# lightdimmer_rc.net
KiCad netlist of a schematic drawn in EAGLE
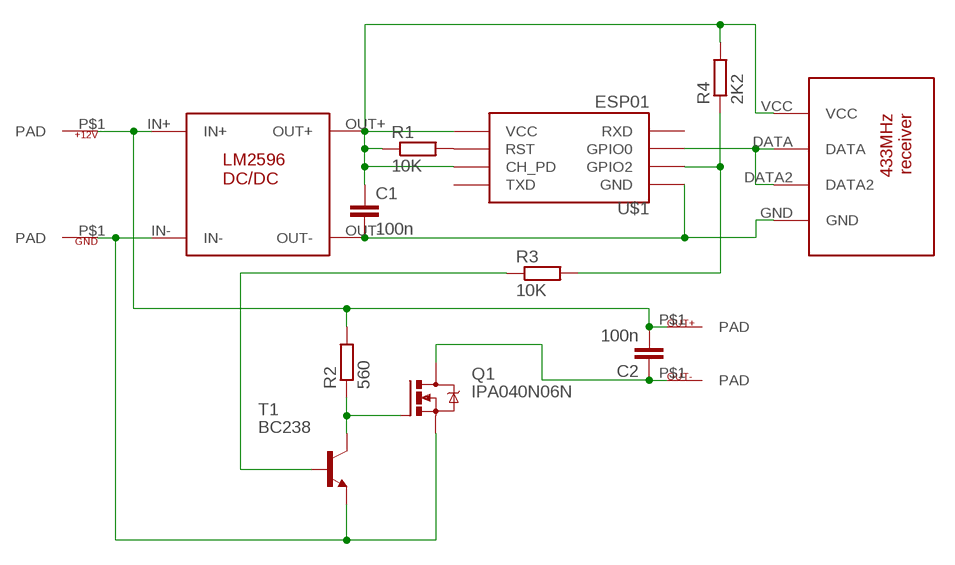
[diagram p0: schematic, sheet 1]

(export (version "E")
  (design (tool "Eeschema 10.0.6"))
  (components
    (comp (ref "+12V")
      (value "PAD")
      (footprint "eagle-import:PAD")
      (libsource (lib "eagle-import") (part "PAD"))
    )
    (comp (ref "C1")
      (value "100n")
      (footprint "eagle-import:C050-025X075")
      (libsource (lib "eagle-import") (part "C-EU050-025X075"))
    )
    (comp (ref "C2")
      (value "100n")
      (footprint "eagle-import:C050-025X075")
      (libsource (lib "eagle-import") (part "C-EU050-025X075"))
    )
    (comp (ref "GND")
      (value "PAD")
      (footprint "eagle-import:PAD")
      (libsource (lib "eagle-import") (part "PAD"))
    )
    (comp (ref "OUT+")
      (value "PAD")
      (footprint "eagle-import:PAD")
      (libsource (lib "eagle-import") (part "PAD"))
    )
    (comp (ref "OUT-")
      (value "PAD")
      (footprint "eagle-import:PAD")
      (libsource (lib "eagle-import") (part "PAD"))
    )
    (comp (ref "Q1")
      (value "IPA040N06N")
      (footprint "eagle-import:TO220BV")
      (libsource (lib "eagle-import") (part "IRF520"))
    )
    (comp (ref "R1")
      (value "10K")
      (footprint "eagle-import:0204_7")
      (libsource (lib "eagle-import") (part "R-EU_0204/7"))
    )
    (comp (ref "R2")
      (value "560")
      (footprint "eagle-import:0204_7")
      (libsource (lib "eagle-import") (part "R-EU_0204/7"))
    )
    (comp (ref "R3")
      (value "10K")
      (footprint "eagle-import:0204_7")
      (libsource (lib "eagle-import") (part "R-EU_0204/7"))
    )
    (comp (ref "R4")
      (value "2K2")
      (footprint "eagle-import:0204_7")
      (libsource (lib "eagle-import") (part "R-EU_0204/7"))
    )
    (comp (ref "T1")
      (value "BC238")
      (footprint "eagle-import:TO92-CBE")
      (libsource (lib "eagle-import") (part "-NPN-TO92-CBEBC238"))
    )
    (comp (ref "U$1")
      (value "ESP01")
      (footprint "eagle-import:ESP01")
      (libsource (lib "eagle-import") (part "ESP01"))
    )
    (comp (ref "U$2")
      (value "RECV433MHZ")
      (footprint "eagle-import:RECV433MHZ")
      (libsource (lib "eagle-import") (part "RECV433MHZ"))
    )
    (comp (ref "U$3")
      (value "LM2596DCDC")
      (footprint "eagle-import:LM2596DCDC")
      (libsource (lib "eagle-import") (part "LM2596DCDC"))
    )
  )
  (nets
    (net (code "1") (name "Net-(+12V-PAD)") (class "Default")
      (node (ref "+12V") (pin "P$1") (pinfunction "PAD_P$1") (pintype "bidirectional"))
      (node (ref "C2") (pin "2") (pinfunction "2_2") (pintype "passive"))
      (node (ref "OUT+") (pin "P$1") (pinfunction "PAD_P$1") (pintype "bidirectional"))
      (node (ref "R2") (pin "2") (pinfunction "2_2") (pintype "passive"))
      (node (ref "U$3") (pin "IN+") (pinfunction "IN+_IN+") (pintype "bidirectional"))
    )
    (net (code "2") (name "Net-(C1-Pad1)") (class "Default")
      (node (ref "C1") (pin "1") (pinfunction "1_1") (pintype "passive"))
      (node (ref "R1") (pin "1") (pinfunction "1_1") (pintype "passive"))
      (node (ref "R4") (pin "2") (pinfunction "2_2") (pintype "passive"))
      (node (ref "U$1") (pin "CH_PD") (pinfunction "CH_PD_CH_PD") (pintype "bidirectional"))
      (node (ref "U$1") (pin "VCC") (pinfunction "VCC_VCC") (pintype "bidirectional"))
      (node (ref "U$2") (pin "VCC") (pinfunction "VCC_VCC") (pintype "bidirectional"))
      (node (ref "U$3") (pin "OUT+") (pinfunction "OUT+_OUT+") (pintype "bidirectional"))
    )
    (net (code "3") (name "Net-(C1-Pad2)") (class "Default")
      (node (ref "C1") (pin "2") (pinfunction "2_2") (pintype "passive"))
      (node (ref "U$1") (pin "GND") (pinfunction "GND_GND") (pintype "bidirectional"))
      (node (ref "U$2") (pin "GND") (pinfunction "GND_GND") (pintype "bidirectional"))
      (node (ref "U$3") (pin "OUT-") (pinfunction "OUT-_OUT-") (pintype "bidirectional"))
    )
    (net (code "4") (name "Net-(GND-PAD)") (class "Default")
      (node (ref "GND") (pin "P$1") (pinfunction "PAD_P$1") (pintype "bidirectional"))
      (node (ref "Q1") (pin "S") (pinfunction "S_S") (pintype "passive"))
      (node (ref "T1") (pin "E") (pinfunction "E_E") (pintype "passive"))
      (node (ref "U$3") (pin "IN-") (pinfunction "IN-_IN-") (pintype "bidirectional"))
    )
    (net (code "5") (name "Net-(OUT--PAD)") (class "Default")
      (node (ref "C2") (pin "1") (pinfunction "1_1") (pintype "passive"))
      (node (ref "OUT-") (pin "P$1") (pinfunction "PAD_P$1") (pintype "bidirectional"))
      (node (ref "Q1") (pin "D") (pinfunction "D_D") (pintype "passive"))
    )
    (net (code "6") (name "Net-(Q1-PadG)") (class "Default")
      (node (ref "Q1") (pin "G") (pinfunction "G_G") (pintype "passive"))
      (node (ref "R2") (pin "1") (pinfunction "1_1") (pintype "passive"))
      (node (ref "T1") (pin "C") (pinfunction "C_C") (pintype "passive"))
    )
    (net (code "7") (name "Net-(R1-Pad2)") (class "Default")
      (node (ref "R1") (pin "2") (pinfunction "2_2") (pintype "passive"))
      (node (ref "U$1") (pin "RST") (pinfunction "RST_RST") (pintype "bidirectional"))
    )
    (net (code "8") (name "Net-(R3-Pad1)") (class "Default")
      (node (ref "R3") (pin "1") (pinfunction "1_1") (pintype "passive"))
      (node (ref "T1") (pin "B") (pinfunction "B_B") (pintype "passive"))
    )
    (net (code "9") (name "Net-(R3-Pad2)") (class "Default")
      (node (ref "R3") (pin "2") (pinfunction "2_2") (pintype "passive"))
      (node (ref "R4") (pin "1") (pinfunction "1_1") (pintype "passive"))
      (node (ref "U$1") (pin "GPIO2") (pinfunction "GPIO2_GPIO2") (pintype "bidirectional"))
    )
    (net (code "10") (name "Net-(U$1-PadGPIO0)") (class "Default")
      (node (ref "U$1") (pin "GPIO0") (pinfunction "GPIO0_GPIO0") (pintype "bidirectional"))
      (node (ref "U$2") (pin "DATA") (pinfunction "DATA_DATA") (pintype "bidirectional"))
      (node (ref "U$2") (pin "DATA2") (pinfunction "DATA2_DATA2") (pintype "bidirectional"))
    )
    (net (code "11") (name "unconnected-(U$1-RXD-PadRX)") (class "Default")
      (node (ref "U$1") (pin "RX") (pinfunction "RXD_RX") (pintype "bidirectional"))
    )
    (net (code "12") (name "unconnected-(U$1-TXD-PadTX)") (class "Default")
      (node (ref "U$1") (pin "TX") (pinfunction "TXD_TX") (pintype "bidirectional"))
    )
  )
)
